# F4_DFC.net
KiCad netlist of a schematic drawn in Altium Designer
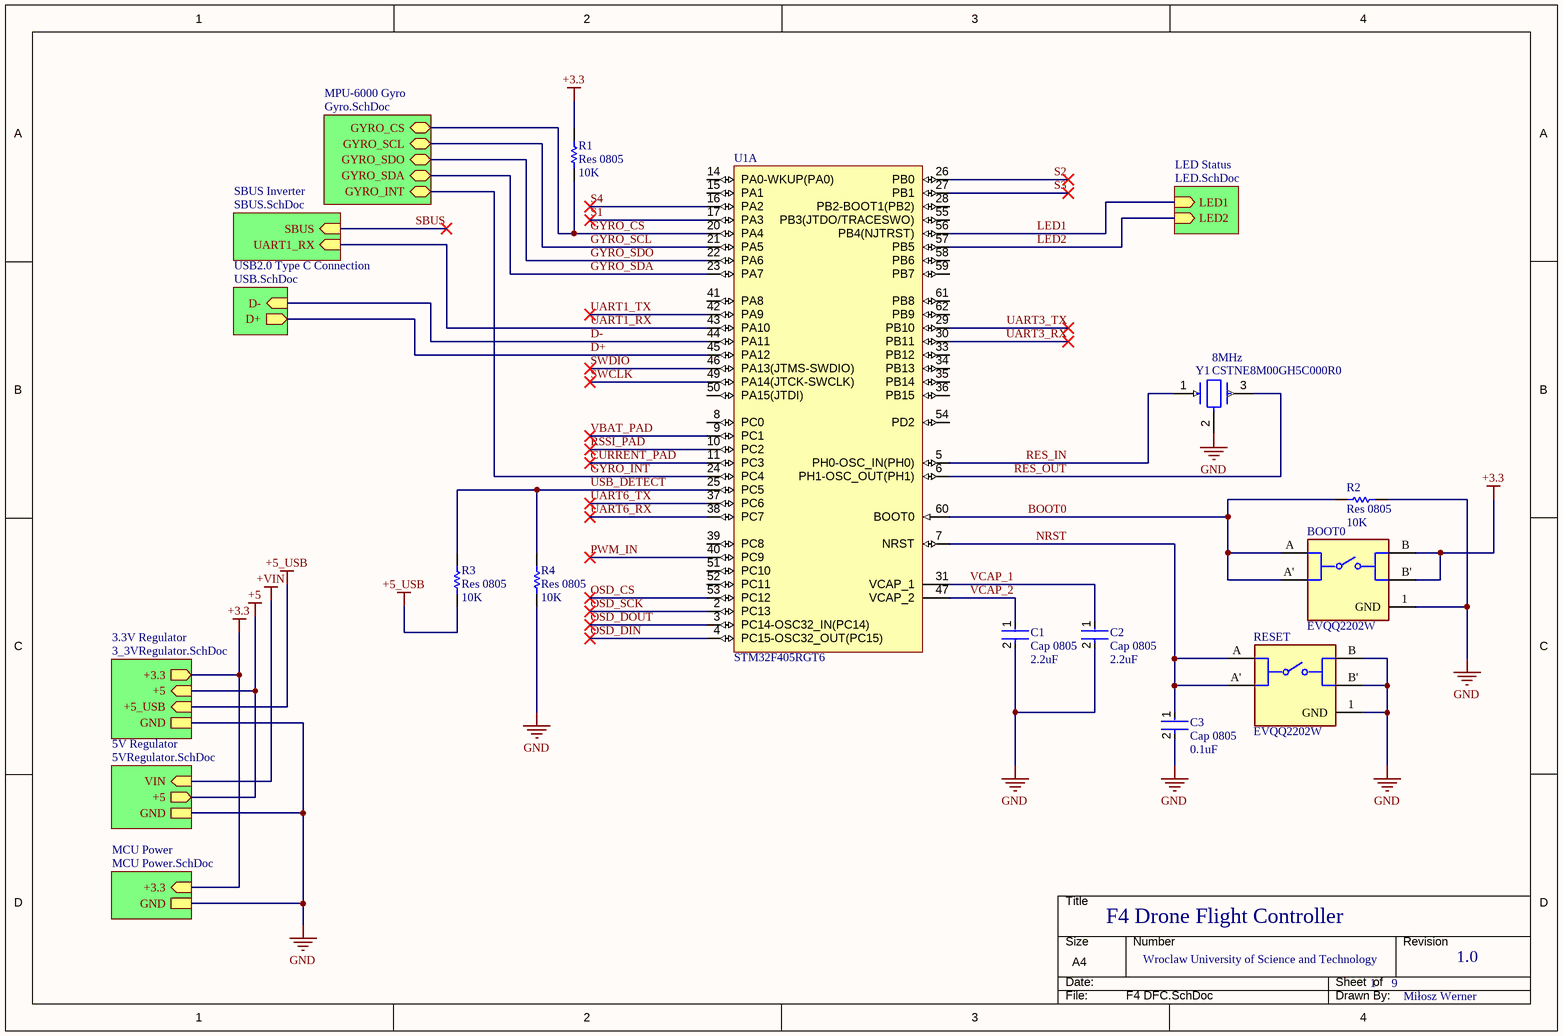
[diagram p0: F4 DFC.SchDoc]

(export (version "E")
  (design (tool "Eeschema 10.0.6"))
  (components
    (comp (ref "BOOT0")
      (value "EVQQ2202W")
      (footprint "FP-EVQQ2202W-MFG")
      (description "SWITCH TACTILE SPST-NO 0.02A 15V")
      (libsource (lib "Altium Content Vault") (part "2aa1f238b7e4ac0bad4b8f7092ac592"))
    )
    (comp (ref "C1")
      (value "Cap 0805")
      (footprint "FP-GRM216-0_1-IPC_C")
      (description "Capacitor")
      (fields (field (name "ALTIUM_VALUE") "2.2uF"))
      (libsource (lib "Altium Content Vault") (part "236180d848d6139a670b325ea6854c9"))
    )
    (comp (ref "C2")
      (value "Cap 0805")
      (footprint "FP-GRM216-0_1-IPC_C")
      (description "Capacitor")
      (fields (field (name "ALTIUM_VALUE") "2.2uF"))
      (libsource (lib "Altium Content Vault") (part "236180d848d6139a670b325ea6854c9"))
    )
    (comp (ref "C3")
      (value "Cap 0805")
      (footprint "FP-GRM216-0_1-IPC_C")
      (description "Capacitor")
      (fields (field (name "ALTIUM_VALUE") "0.1uF"))
      (libsource (lib "Altium Content Vault") (part "236180d848d6139a670b325ea6854c9"))
    )
    (comp (ref "R1")
      (value "Res 0805")
      (footprint "RESC2013X50X30LL20T20")
      (description "Resistor")
      (fields (field (name "ALTIUM_VALUE") "10K"))
      (libsource (lib "Altium Content Vault") (part "RES"))
    )
    (comp (ref "R2")
      (value "Res 0805")
      (footprint "RESC2013X50X30LL20T20")
      (description "Resistor")
      (fields (field (name "ALTIUM_VALUE") "10K"))
      (libsource (lib "Altium Content Vault") (part "RES"))
    )
    (comp (ref "R3")
      (value "Res 0805")
      (footprint "RESC2013X50X30LL20T20")
      (description "Resistor")
      (fields (field (name "ALTIUM_VALUE") "10K"))
      (libsource (lib "Altium Content Vault") (part "RES"))
    )
    (comp (ref "R4")
      (value "Res 0805")
      (footprint "RESC2013X50X30LL20T20")
      (description "Resistor")
      (fields (field (name "ALTIUM_VALUE") "10K"))
      (libsource (lib "Altium Content Vault") (part "RES"))
    )
    (comp (ref "RESET")
      (value "EVQQ2202W")
      (footprint "FP-EVQQ2202W-MFG")
      (description "SWITCH TACTILE SPST-NO 0.02A 15V")
      (libsource (lib "Altium Content Vault") (part "2aa1f238b7e4ac0bad4b8f7092ac592"))
    )
    (comp (ref "U1")
      (value "STM32F405RGT6")
      (footprint "STM-LQFP64_V")
      (fields (field (name "MANUFACTURER") "STMicroelectronics"))
      (libsource (lib "Altium Content Vault") (part "MC-ARM-STM32F4X5-SQ64"))
    )
    (comp (ref "Y1")
      (value "CSTNE8M00GH5C000R0")
      (footprint "FP-CSTNE8M00GH5C000R0-MFG")
      (description "CERAMIC RES 8.0000MHZ 33PF SMD")
      (fields (field (name "ALTIUM_VALUE") "8MHz"))
      (libsource (lib "Altium Content Vault") (part "7d37667f5012bb31280c8009ddd0b1c"))
    )
  )
  (nets
    (net (code "1") (name "+3.3") (class "Default")
      (node (ref "BOOT0") (pin "B") (pinfunction "B_B") (pintype "passive"))
      (node (ref "BOOT0") (pin "B'") (pinfunction "B'_B'") (pintype "passive"))
      (node (ref "R1") (pin "2") (pinfunction "2_2") (pintype "passive"))
    )
    (net (code "3") (name "+5_USB") (class "Default")
      (node (ref "R3") (pin "1") (pinfunction "1_1") (pintype "passive"))
    )
    (net (code "5") (name "/BOOT0") (class "Default")
      (node (ref "BOOT0") (pin "A") (pinfunction "A_A") (pintype "passive"))
      (node (ref "BOOT0") (pin "A'") (pinfunction "A'_A'") (pintype "passive"))
      (node (ref "R2") (pin "2") (pinfunction "2_2") (pintype "passive"))
      (node (ref "U1") (pin "60") (pinfunction "BOOT0_60") (pintype "input"))
    )
    (net (code "6") (name "/CURRENT_PAD") (class "Default")
      (node (ref "U1") (pin "11") (pinfunction "PC3_11") (pintype "bidirectional+no_connect"))
    )
    (net (code "7") (name "/D+") (class "Default")
      (node (ref "U1") (pin "45") (pinfunction "PA12_45") (pintype "bidirectional"))
    )
    (net (code "8") (name "/D-") (class "Default")
      (node (ref "U1") (pin "44") (pinfunction "PA11_44") (pintype "bidirectional"))
    )
    (net (code "9") (name "/GYRO_CS") (class "Default")
      (node (ref "R1") (pin "1") (pinfunction "1_1") (pintype "passive"))
      (node (ref "U1") (pin "20") (pinfunction "PA4_20") (pintype "bidirectional"))
    )
    (net (code "10") (name "/GYRO_INT") (class "Default")
      (node (ref "U1") (pin "24") (pinfunction "PC4_24") (pintype "bidirectional"))
    )
    (net (code "11") (name "/GYRO_SCL") (class "Default")
      (node (ref "U1") (pin "21") (pinfunction "PA5_21") (pintype "bidirectional"))
    )
    (net (code "12") (name "/GYRO_SDA") (class "Default")
      (node (ref "U1") (pin "23") (pinfunction "PA7_23") (pintype "bidirectional"))
    )
    (net (code "13") (name "/GYRO_SDO") (class "Default")
      (node (ref "U1") (pin "22") (pinfunction "PA6_22") (pintype "bidirectional"))
    )
    (net (code "14") (name "/LED1") (class "Default")
      (node (ref "U1") (pin "56") (pinfunction "PB4(NJTRST)_56") (pintype "bidirectional"))
    )
    (net (code "15") (name "/LED2") (class "Default")
      (node (ref "U1") (pin "57") (pinfunction "PB5_57") (pintype "bidirectional"))
    )
    (net (code "16") (name "/NRST") (class "Default")
      (node (ref "C3") (pin "1") (pinfunction "1_1") (pintype "passive"))
      (node (ref "RESET") (pin "A") (pinfunction "A_A") (pintype "passive"))
      (node (ref "RESET") (pin "A'") (pinfunction "A'_A'") (pintype "passive"))
      (node (ref "U1") (pin "7") (pinfunction "NRST_7") (pintype "bidirectional"))
    )
    (net (code "17") (name "/OSD_CS") (class "Default")
      (node (ref "U1") (pin "53") (pinfunction "PC12_53") (pintype "bidirectional+no_connect"))
    )
    (net (code "18") (name "/OSD_DIN") (class "Default")
      (node (ref "U1") (pin "4") (pinfunction "PC15-OSC32_OUT(PC15)_4") (pintype "bidirectional+no_connect"))
    )
    (net (code "19") (name "/OSD_DOUT") (class "Default")
      (node (ref "U1") (pin "3") (pinfunction "PC14-OSC32_IN(PC14)_3") (pintype "bidirectional+no_connect"))
    )
    (net (code "20") (name "/OSD_SCK") (class "Default")
      (node (ref "U1") (pin "2") (pinfunction "PC13_2") (pintype "bidirectional+no_connect"))
    )
    (net (code "21") (name "/PWM_IN") (class "Default")
      (node (ref "U1") (pin "40") (pinfunction "PC9_40") (pintype "bidirectional+no_connect"))
    )
    (net (code "22") (name "/RES_IN") (class "Default")
      (node (ref "U1") (pin "5") (pinfunction "PH0-OSC_IN(PH0)_5") (pintype "bidirectional"))
      (node (ref "Y1") (pin "1") (pinfunction "Input_1") (pintype "input"))
    )
    (net (code "23") (name "/RES_OUT") (class "Default")
      (node (ref "U1") (pin "6") (pinfunction "PH1-OSC_OUT(PH1)_6") (pintype "bidirectional"))
      (node (ref "Y1") (pin "3") (pinfunction "Output_3") (pintype "output"))
    )
    (net (code "24") (name "/RSSI_PAD") (class "Default")
      (node (ref "U1") (pin "10") (pinfunction "PC2_10") (pintype "bidirectional+no_connect"))
    )
    (net (code "25") (name "/S1") (class "Default")
      (node (ref "U1") (pin "17") (pinfunction "PA3_17") (pintype "bidirectional+no_connect"))
    )
    (net (code "26") (name "/S2") (class "Default")
      (node (ref "U1") (pin "26") (pinfunction "PB0_26") (pintype "bidirectional+no_connect"))
    )
    (net (code "27") (name "/S3") (class "Default")
      (node (ref "U1") (pin "27") (pinfunction "PB1_27") (pintype "bidirectional+no_connect"))
    )
    (net (code "28") (name "/S4") (class "Default")
      (node (ref "U1") (pin "16") (pinfunction "PA2_16") (pintype "bidirectional+no_connect"))
    )
    (net (code "30") (name "/SWCLK") (class "Default")
      (node (ref "U1") (pin "49") (pinfunction "PA14(JTCK-SWCLK)_49") (pintype "bidirectional+no_connect"))
    )
    (net (code "31") (name "/SWDIO") (class "Default")
      (node (ref "U1") (pin "46") (pinfunction "PA13(JTMS-SWDIO)_46") (pintype "bidirectional+no_connect"))
    )
    (net (code "32") (name "/UART1_RX") (class "Default")
      (node (ref "U1") (pin "43") (pinfunction "PA10_43") (pintype "bidirectional"))
    )
    (net (code "33") (name "/UART1_TX") (class "Default")
      (node (ref "U1") (pin "42") (pinfunction "PA9_42") (pintype "bidirectional+no_connect"))
    )
    (net (code "34") (name "/UART3_RX") (class "Default")
      (node (ref "U1") (pin "30") (pinfunction "PB11_30") (pintype "bidirectional+no_connect"))
    )
    (net (code "35") (name "/UART3_TX") (class "Default")
      (node (ref "U1") (pin "29") (pinfunction "PB10_29") (pintype "bidirectional+no_connect"))
    )
    (net (code "36") (name "/UART6_RX") (class "Default")
      (node (ref "U1") (pin "38") (pinfunction "PC7_38") (pintype "bidirectional+no_connect"))
    )
    (net (code "37") (name "/UART6_TX") (class "Default")
      (node (ref "U1") (pin "37") (pinfunction "PC6_37") (pintype "bidirectional+no_connect"))
    )
    (net (code "38") (name "/USB_DETECT") (class "Default")
      (node (ref "R3") (pin "2") (pinfunction "2_2") (pintype "passive"))
      (node (ref "R4") (pin "2") (pinfunction "2_2") (pintype "passive"))
      (node (ref "U1") (pin "25") (pinfunction "PC5_25") (pintype "bidirectional"))
    )
    (net (code "39") (name "/VBAT_PAD") (class "Default")
      (node (ref "U1") (pin "9") (pinfunction "PC1_9") (pintype "bidirectional+no_connect"))
    )
    (net (code "40") (name "/VCAP_1") (class "Default")
      (node (ref "C2") (pin "1") (pinfunction "1_1") (pintype "passive"))
      (node (ref "U1") (pin "31") (pinfunction "VCAP_1_31") (pintype "power_in"))
    )
    (net (code "41") (name "/VCAP_2") (class "Default")
      (node (ref "C1") (pin "1") (pinfunction "1_1") (pintype "passive"))
      (node (ref "U1") (pin "47") (pinfunction "VCAP_2_47") (pintype "power_in"))
    )
    (net (code "42") (name "GND") (class "Default")
      (node (ref "BOOT0") (pin "1") (pinfunction "GND_1") (pintype "power_in"))
      (node (ref "C1") (pin "2") (pinfunction "2_2") (pintype "passive"))
      (node (ref "C2") (pin "2") (pinfunction "2_2") (pintype "passive"))
      (node (ref "C3") (pin "2") (pinfunction "2_2") (pintype "passive"))
      (node (ref "R2") (pin "1") (pinfunction "1_1") (pintype "passive"))
      (node (ref "R4") (pin "1") (pinfunction "1_1") (pintype "passive"))
      (node (ref "RESET") (pin "1") (pinfunction "GND_1") (pintype "power_in"))
      (node (ref "RESET") (pin "B") (pinfunction "B_B") (pintype "passive"))
      (node (ref "RESET") (pin "B'") (pinfunction "B'_B'") (pintype "passive"))
      (node (ref "Y1") (pin "2") (pinfunction "GND_2") (pintype "power_in"))
    )
    (net (code "43") (name "unconnected-(U1A-PA0-WKUP(PA0)-Pad14)") (class "Default")
      (node (ref "U1") (pin "14") (pinfunction "PA0-WKUP(PA0)_14") (pintype "bidirectional"))
    )
    (net (code "44") (name "unconnected-(U1A-PA1-Pad15)") (class "Default")
      (node (ref "U1") (pin "15") (pinfunction "PA1_15") (pintype "bidirectional"))
    )
    (net (code "45") (name "unconnected-(U1A-PA8-Pad41)") (class "Default")
      (node (ref "U1") (pin "41") (pinfunction "PA8_41") (pintype "bidirectional"))
    )
    (net (code "46") (name "unconnected-(U1A-PA15(JTDI)-Pad50)") (class "Default")
      (node (ref "U1") (pin "50") (pinfunction "PA15(JTDI)_50") (pintype "bidirectional"))
    )
    (net (code "47") (name "unconnected-(U1A-PB2-BOOT1(PB2)-Pad28)") (class "Default")
      (node (ref "U1") (pin "28") (pinfunction "PB2-BOOT1(PB2)_28") (pintype "bidirectional"))
    )
    (net (code "48") (name "unconnected-(U1A-PB3(JTDO{slash}TRACESWO)-Pad55)") (class "Default")
      (node (ref "U1") (pin "55") (pinfunction "PB3(JTDO/TRACESWO)_55") (pintype "bidirectional"))
    )
    (net (code "49") (name "unconnected-(U1A-PB6-Pad58)") (class "Default")
      (node (ref "U1") (pin "58") (pinfunction "PB6_58") (pintype "bidirectional"))
    )
    (net (code "50") (name "unconnected-(U1A-PB7-Pad59)") (class "Default")
      (node (ref "U1") (pin "59") (pinfunction "PB7_59") (pintype "bidirectional"))
    )
    (net (code "51") (name "unconnected-(U1A-PB8-Pad61)") (class "Default")
      (node (ref "U1") (pin "61") (pinfunction "PB8_61") (pintype "bidirectional"))
    )
    (net (code "52") (name "unconnected-(U1A-PB9-Pad62)") (class "Default")
      (node (ref "U1") (pin "62") (pinfunction "PB9_62") (pintype "bidirectional"))
    )
    (net (code "53") (name "unconnected-(U1A-PB12-Pad33)") (class "Default")
      (node (ref "U1") (pin "33") (pinfunction "PB12_33") (pintype "bidirectional"))
    )
    (net (code "54") (name "unconnected-(U1A-PB13-Pad34)") (class "Default")
      (node (ref "U1") (pin "34") (pinfunction "PB13_34") (pintype "bidirectional"))
    )
    (net (code "55") (name "unconnected-(U1A-PB14-Pad35)") (class "Default")
      (node (ref "U1") (pin "35") (pinfunction "PB14_35") (pintype "bidirectional"))
    )
    (net (code "56") (name "unconnected-(U1A-PB15-Pad36)") (class "Default")
      (node (ref "U1") (pin "36") (pinfunction "PB15_36") (pintype "bidirectional"))
    )
    (net (code "57") (name "unconnected-(U1A-PC0-Pad8)") (class "Default")
      (node (ref "U1") (pin "8") (pinfunction "PC0_8") (pintype "bidirectional"))
    )
    (net (code "58") (name "unconnected-(U1A-PC8-Pad39)") (class "Default")
      (node (ref "U1") (pin "39") (pinfunction "PC8_39") (pintype "bidirectional"))
    )
    (net (code "59") (name "unconnected-(U1A-PC10-Pad51)") (class "Default")
      (node (ref "U1") (pin "51") (pinfunction "PC10_51") (pintype "bidirectional"))
    )
    (net (code "60") (name "unconnected-(U1A-PC11-Pad52)") (class "Default")
      (node (ref "U1") (pin "52") (pinfunction "PC11_52") (pintype "bidirectional"))
    )
    (net (code "61") (name "unconnected-(U1A-PD2-Pad54)") (class "Default")
      (node (ref "U1") (pin "54") (pinfunction "PD2_54") (pintype "bidirectional"))
    )
  )
)
